# tinyadder_r3.net
KiCad netlist of a schematic drawn in EAGLE
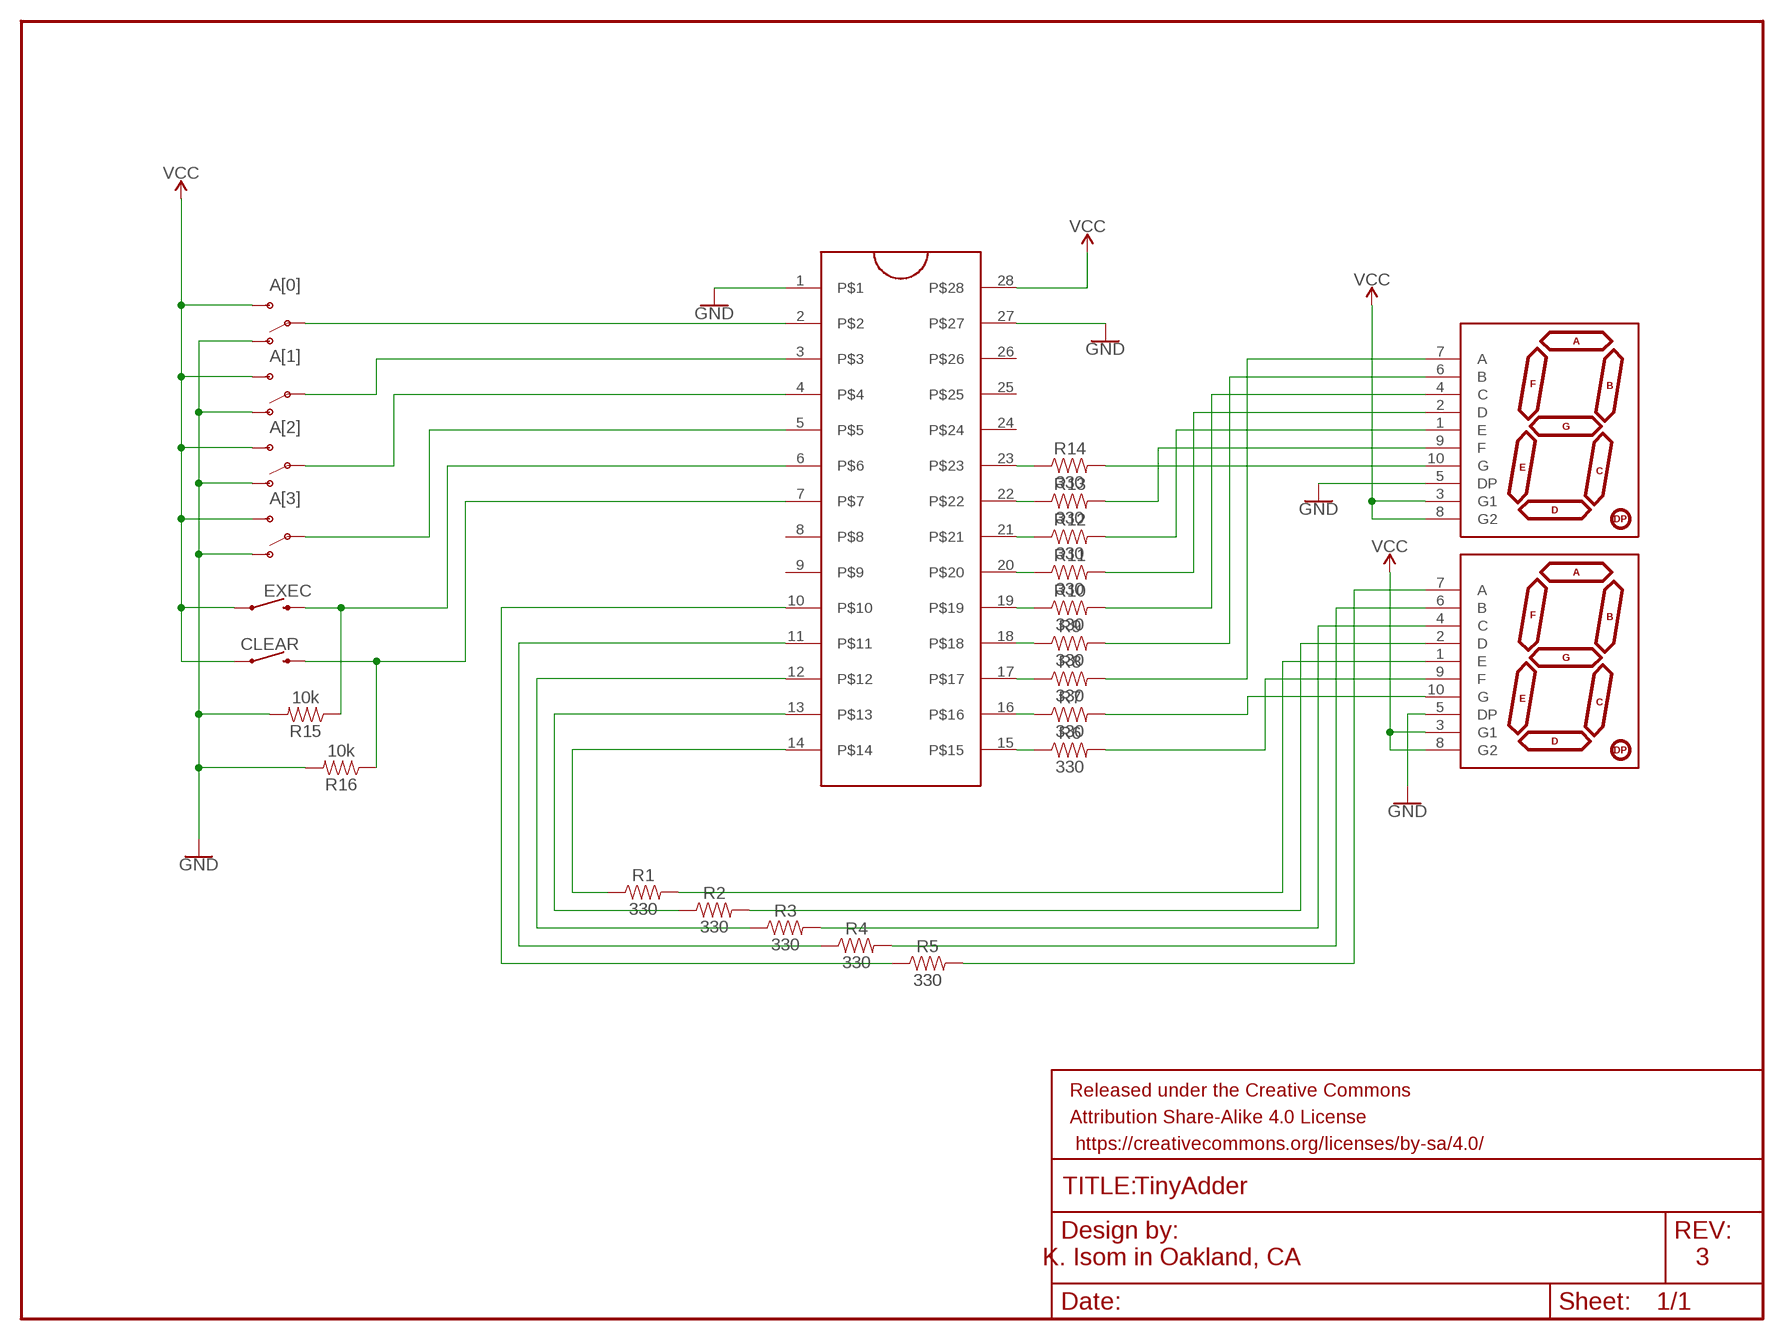
[diagram p0: schematic, sheet 1]

(export (version "E")
  (design (tool "Eeschema 10.0.6"))
  (components
    (comp (ref "A[0]")
      (value "SWITCH-SPDT-PTH-11.6X4.0MM")
      (footprint "eagle-import:SWITCH_SPDT_PTH_11.6X4.0MM")
      (libsource (lib "eagle-import") (part "SWITCH-SPDT-PTH-11.6X4.0MM"))
    )
    (comp (ref "A[1]")
      (value "SWITCH-SPDT-PTH-11.6X4.0MM")
      (footprint "eagle-import:SWITCH_SPDT_PTH_11.6X4.0MM")
      (libsource (lib "eagle-import") (part "SWITCH-SPDT-PTH-11.6X4.0MM"))
    )
    (comp (ref "A[2]")
      (value "SWITCH-SPDT-PTH-11.6X4.0MM")
      (footprint "eagle-import:SWITCH_SPDT_PTH_11.6X4.0MM")
      (libsource (lib "eagle-import") (part "SWITCH-SPDT-PTH-11.6X4.0MM"))
    )
    (comp (ref "A[3]")
      (value "SWITCH-SPDT-PTH-11.6X4.0MM")
      (footprint "eagle-import:SWITCH_SPDT_PTH_11.6X4.0MM")
      (libsource (lib "eagle-import") (part "SWITCH-SPDT-PTH-11.6X4.0MM"))
    )
    (comp (ref "CLEAR")
      (value "MOMENTARY-SWITCH-SPST-PTH-6.0MM")
      (footprint "eagle-import:TACTILE_SWITCH_PTH_6.0MM")
      (libsource (lib "eagle-import") (part "MOMENTARY-SWITCH-SPST-PTH-6.0MM"))
    )
    (comp (ref "EXEC")
      (value "MOMENTARY-SWITCH-SPST-PTH-6.0MM")
      (footprint "eagle-import:TACTILE_SWITCH_PTH_6.0MM")
      (libsource (lib "eagle-import") (part "MOMENTARY-SWITCH-SPST-PTH-6.0MM"))
    )
    (comp (ref "FRAME1")
      (value "FRAME-LETTER")
      (footprint "eagle-import:CREATIVE_COMMONS")
      (libsource (lib "eagle-import") (part "FRAME-LETTER"))
    )
    (comp (ref "J1")
      (value "ZIFSOCKET-28-3\"")
      (footprint "eagle-import:DIL28-3-ZIF_SOCKET")
      (libsource (lib "eagle-import") (part "ZIFSOCKET-28-3{dblquote}"))
    )
    (comp (ref "R1")
      (value "330")
      (footprint "eagle-import:AXIAL-0.3")
      (libsource (lib "eagle-import") (part "330OHM-HORIZ-1/10W-5%"))
    )
    (comp (ref "R2")
      (value "330")
      (footprint "eagle-import:AXIAL-0.3")
      (libsource (lib "eagle-import") (part "330OHM-HORIZ-1/10W-5%"))
    )
    (comp (ref "R3")
      (value "330")
      (footprint "eagle-import:AXIAL-0.3")
      (libsource (lib "eagle-import") (part "330OHM-HORIZ-1/10W-5%"))
    )
    (comp (ref "R4")
      (value "330")
      (footprint "eagle-import:AXIAL-0.3")
      (libsource (lib "eagle-import") (part "330OHM-HORIZ-1/10W-5%"))
    )
    (comp (ref "R5")
      (value "330")
      (footprint "eagle-import:AXIAL-0.3")
      (libsource (lib "eagle-import") (part "330OHM-HORIZ-1/10W-5%"))
    )
    (comp (ref "R6")
      (value "330")
      (footprint "eagle-import:AXIAL-0.3")
      (libsource (lib "eagle-import") (part "330OHM-HORIZ-1/10W-5%"))
    )
    (comp (ref "R7")
      (value "330")
      (footprint "eagle-import:AXIAL-0.3")
      (libsource (lib "eagle-import") (part "330OHM-HORIZ-1/10W-5%"))
    )
    (comp (ref "R8")
      (value "330")
      (footprint "eagle-import:AXIAL-0.3")
      (libsource (lib "eagle-import") (part "330OHM-HORIZ-1/10W-5%"))
    )
    (comp (ref "R9")
      (value "330")
      (footprint "eagle-import:AXIAL-0.3")
      (libsource (lib "eagle-import") (part "330OHM-HORIZ-1/10W-5%"))
    )
    (comp (ref "R10")
      (value "330")
      (footprint "eagle-import:AXIAL-0.3")
      (libsource (lib "eagle-import") (part "330OHM-HORIZ-1/10W-5%"))
    )
    (comp (ref "R11")
      (value "330")
      (footprint "eagle-import:AXIAL-0.3")
      (libsource (lib "eagle-import") (part "330OHM-HORIZ-1/10W-5%"))
    )
    (comp (ref "R12")
      (value "330")
      (footprint "eagle-import:AXIAL-0.3")
      (libsource (lib "eagle-import") (part "330OHM-HORIZ-1/10W-5%"))
    )
    (comp (ref "R13")
      (value "330")
      (footprint "eagle-import:AXIAL-0.3")
      (libsource (lib "eagle-import") (part "330OHM-HORIZ-1/10W-5%"))
    )
    (comp (ref "R14")
      (value "330")
      (footprint "eagle-import:AXIAL-0.3")
      (libsource (lib "eagle-import") (part "330OHM-HORIZ-1/10W-5%"))
    )
    (comp (ref "R15")
      (value "10k")
      (footprint "eagle-import:AXIAL-0.3")
      (libsource (lib "eagle-import") (part "10KOHM-HORIZ-1/4W-1%"))
    )
    (comp (ref "R16")
      (value "10k")
      (footprint "eagle-import:AXIAL-0.3")
      (libsource (lib "eagle-import") (part "10KOHM-HORIZ-1/4W-1%"))
    )
    (comp (ref "U$1")
      (value "YSD-1601AR4B-8")
      (footprint "eagle-import:7-SEGMENT-1_PTH")
      (libsource (lib "eagle-import") (part "7-SEGMENT-1DIGIT-1INCH-RED"))
    )
    (comp (ref "U$2")
      (value "YSD-1601AR4B-8")
      (footprint "eagle-import:7-SEGMENT-1_PTH")
      (libsource (lib "eagle-import") (part "7-SEGMENT-1DIGIT-1INCH-RED"))
    )
  )
  (nets
    (net (code "1") (name "GND") (class "Default")
      (node (ref "A[0]") (pin "1") (pinfunction "O_1") (pintype "passive"))
      (node (ref "A[1]") (pin "1") (pinfunction "O_1") (pintype "passive"))
      (node (ref "A[2]") (pin "1") (pinfunction "O_1") (pintype "passive"))
      (node (ref "A[3]") (pin "1") (pinfunction "O_1") (pintype "passive"))
      (node (ref "J1") (pin "1") (pinfunction "P$1_1") (pintype "bidirectional"))
      (node (ref "J1") (pin "27") (pinfunction "P$27_27") (pintype "bidirectional"))
      (node (ref "R15") (pin "P$2") (pinfunction "2_P$2") (pintype "passive"))
      (node (ref "R16") (pin "P$2") (pinfunction "2_P$2") (pintype "passive"))
      (node (ref "U$1") (pin "5") (pinfunction "DP_5") (pintype "bidirectional"))
      (node (ref "U$2") (pin "5") (pinfunction "DP_5") (pintype "bidirectional"))
    )
    (net (code "2") (name "Net-(A[0]-P)") (class "Default")
      (node (ref "A[0]") (pin "2") (pinfunction "P_2") (pintype "passive"))
      (node (ref "J1") (pin "2") (pinfunction "P$2_2") (pintype "bidirectional"))
    )
    (net (code "3") (name "Net-(A[1]-P)") (class "Default")
      (node (ref "A[1]") (pin "2") (pinfunction "P_2") (pintype "passive"))
      (node (ref "J1") (pin "3") (pinfunction "P$3_3") (pintype "bidirectional"))
    )
    (net (code "4") (name "Net-(A[2]-P)") (class "Default")
      (node (ref "A[2]") (pin "2") (pinfunction "P_2") (pintype "passive"))
      (node (ref "J1") (pin "4") (pinfunction "P$4_4") (pintype "bidirectional"))
    )
    (net (code "5") (name "Net-(A[3]-P)") (class "Default")
      (node (ref "A[3]") (pin "2") (pinfunction "P_2") (pintype "passive"))
      (node (ref "J1") (pin "5") (pinfunction "P$5_5") (pintype "bidirectional"))
    )
    (net (code "6") (name "Net-(CLEAR-2)") (class "Default")
      (node (ref "CLEAR") (pin "3") (pinfunction "2_3") (pintype "passive"))
      (node (ref "J1") (pin "7") (pinfunction "P$7_7") (pintype "bidirectional"))
      (node (ref "R16") (pin "P$1") (pinfunction "1_P$1") (pintype "passive"))
    )
    (net (code "7") (name "Net-(EXEC-2)") (class "Default")
      (node (ref "EXEC") (pin "3") (pinfunction "2_3") (pintype "passive"))
      (node (ref "J1") (pin "6") (pinfunction "P$6_6") (pintype "bidirectional"))
      (node (ref "R15") (pin "P$1") (pinfunction "1_P$1") (pintype "passive"))
    )
    (net (code "8") (name "Net-(J1-P$10)") (class "Default")
      (node (ref "J1") (pin "10") (pinfunction "P$10_10") (pintype "bidirectional"))
      (node (ref "R5") (pin "P$1") (pinfunction "1_P$1") (pintype "passive"))
    )
    (net (code "9") (name "Net-(J1-P$11)") (class "Default")
      (node (ref "J1") (pin "11") (pinfunction "P$11_11") (pintype "bidirectional"))
      (node (ref "R4") (pin "P$1") (pinfunction "1_P$1") (pintype "passive"))
    )
    (net (code "10") (name "Net-(J1-P$12)") (class "Default")
      (node (ref "J1") (pin "12") (pinfunction "P$12_12") (pintype "bidirectional"))
      (node (ref "R3") (pin "P$1") (pinfunction "1_P$1") (pintype "passive"))
    )
    (net (code "11") (name "Net-(J1-P$13)") (class "Default")
      (node (ref "J1") (pin "13") (pinfunction "P$13_13") (pintype "bidirectional"))
      (node (ref "R2") (pin "P$1") (pinfunction "1_P$1") (pintype "passive"))
    )
    (net (code "12") (name "Net-(J1-P$14)") (class "Default")
      (node (ref "J1") (pin "14") (pinfunction "P$14_14") (pintype "bidirectional"))
      (node (ref "R1") (pin "P$1") (pinfunction "1_P$1") (pintype "passive"))
    )
    (net (code "13") (name "Net-(J1-P$15)") (class "Default")
      (node (ref "J1") (pin "15") (pinfunction "P$15_15") (pintype "bidirectional"))
      (node (ref "R6") (pin "P$1") (pinfunction "1_P$1") (pintype "passive"))
    )
    (net (code "14") (name "Net-(J1-P$16)") (class "Default")
      (node (ref "J1") (pin "16") (pinfunction "P$16_16") (pintype "bidirectional"))
      (node (ref "R7") (pin "P$1") (pinfunction "1_P$1") (pintype "passive"))
    )
    (net (code "15") (name "Net-(J1-P$17)") (class "Default")
      (node (ref "J1") (pin "17") (pinfunction "P$17_17") (pintype "bidirectional"))
      (node (ref "R8") (pin "P$1") (pinfunction "1_P$1") (pintype "passive"))
    )
    (net (code "16") (name "Net-(J1-P$18)") (class "Default")
      (node (ref "J1") (pin "18") (pinfunction "P$18_18") (pintype "bidirectional"))
      (node (ref "R9") (pin "P$1") (pinfunction "1_P$1") (pintype "passive"))
    )
    (net (code "17") (name "Net-(J1-P$19)") (class "Default")
      (node (ref "J1") (pin "19") (pinfunction "P$19_19") (pintype "bidirectional"))
      (node (ref "R10") (pin "P$1") (pinfunction "1_P$1") (pintype "passive"))
    )
    (net (code "18") (name "Net-(J1-P$20)") (class "Default")
      (node (ref "J1") (pin "20") (pinfunction "P$20_20") (pintype "bidirectional"))
      (node (ref "R11") (pin "P$1") (pinfunction "1_P$1") (pintype "passive"))
    )
    (net (code "19") (name "Net-(J1-P$21)") (class "Default")
      (node (ref "J1") (pin "21") (pinfunction "P$21_21") (pintype "bidirectional"))
      (node (ref "R12") (pin "P$1") (pinfunction "1_P$1") (pintype "passive"))
    )
    (net (code "20") (name "Net-(J1-P$22)") (class "Default")
      (node (ref "J1") (pin "22") (pinfunction "P$22_22") (pintype "bidirectional"))
      (node (ref "R13") (pin "P$1") (pinfunction "1_P$1") (pintype "passive"))
    )
    (net (code "21") (name "Net-(J1-P$23)") (class "Default")
      (node (ref "J1") (pin "23") (pinfunction "P$23_23") (pintype "bidirectional"))
      (node (ref "R14") (pin "P$1") (pinfunction "1_P$1") (pintype "passive"))
    )
    (net (code "22") (name "Net-(R1-2)") (class "Default")
      (node (ref "R1") (pin "P$2") (pinfunction "2_P$2") (pintype "passive"))
      (node (ref "U$2") (pin "1") (pinfunction "E_1") (pintype "bidirectional"))
    )
    (net (code "23") (name "Net-(R2-2)") (class "Default")
      (node (ref "R2") (pin "P$2") (pinfunction "2_P$2") (pintype "passive"))
      (node (ref "U$2") (pin "2") (pinfunction "D_2") (pintype "bidirectional"))
    )
    (net (code "24") (name "Net-(R3-2)") (class "Default")
      (node (ref "R3") (pin "P$2") (pinfunction "2_P$2") (pintype "passive"))
      (node (ref "U$2") (pin "4") (pinfunction "C_4") (pintype "bidirectional"))
    )
    (net (code "25") (name "Net-(R4-2)") (class "Default")
      (node (ref "R4") (pin "P$2") (pinfunction "2_P$2") (pintype "passive"))
      (node (ref "U$2") (pin "6") (pinfunction "B_6") (pintype "bidirectional"))
    )
    (net (code "26") (name "Net-(R5-2)") (class "Default")
      (node (ref "R5") (pin "P$2") (pinfunction "2_P$2") (pintype "passive"))
      (node (ref "U$2") (pin "7") (pinfunction "A_7") (pintype "bidirectional"))
    )
    (net (code "27") (name "Net-(R6-2)") (class "Default")
      (node (ref "R6") (pin "P$2") (pinfunction "2_P$2") (pintype "passive"))
      (node (ref "U$2") (pin "9") (pinfunction "F_9") (pintype "bidirectional"))
    )
    (net (code "28") (name "Net-(R7-2)") (class "Default")
      (node (ref "R7") (pin "P$2") (pinfunction "2_P$2") (pintype "passive"))
      (node (ref "U$2") (pin "10") (pinfunction "G_10") (pintype "bidirectional"))
    )
    (net (code "29") (name "Net-(R8-2)") (class "Default")
      (node (ref "R8") (pin "P$2") (pinfunction "2_P$2") (pintype "passive"))
      (node (ref "U$1") (pin "7") (pinfunction "A_7") (pintype "bidirectional"))
    )
    (net (code "30") (name "Net-(R9-2)") (class "Default")
      (node (ref "R9") (pin "P$2") (pinfunction "2_P$2") (pintype "passive"))
      (node (ref "U$1") (pin "6") (pinfunction "B_6") (pintype "bidirectional"))
    )
    (net (code "31") (name "Net-(R10-2)") (class "Default")
      (node (ref "R10") (pin "P$2") (pinfunction "2_P$2") (pintype "passive"))
      (node (ref "U$1") (pin "4") (pinfunction "C_4") (pintype "bidirectional"))
    )
    (net (code "32") (name "Net-(R11-2)") (class "Default")
      (node (ref "R11") (pin "P$2") (pinfunction "2_P$2") (pintype "passive"))
      (node (ref "U$1") (pin "2") (pinfunction "D_2") (pintype "bidirectional"))
    )
    (net (code "33") (name "Net-(R12-2)") (class "Default")
      (node (ref "R12") (pin "P$2") (pinfunction "2_P$2") (pintype "passive"))
      (node (ref "U$1") (pin "1") (pinfunction "E_1") (pintype "bidirectional"))
    )
    (net (code "34") (name "Net-(R13-2)") (class "Default")
      (node (ref "R13") (pin "P$2") (pinfunction "2_P$2") (pintype "passive"))
      (node (ref "U$1") (pin "9") (pinfunction "F_9") (pintype "bidirectional"))
    )
    (net (code "35") (name "Net-(R14-2)") (class "Default")
      (node (ref "R14") (pin "P$2") (pinfunction "2_P$2") (pintype "passive"))
      (node (ref "U$1") (pin "10") (pinfunction "G_10") (pintype "bidirectional"))
    )
    (net (code "36") (name "VCC") (class "Default")
      (node (ref "A[0]") (pin "3") (pinfunction "S_3") (pintype "passive"))
      (node (ref "A[1]") (pin "3") (pinfunction "S_3") (pintype "passive"))
      (node (ref "A[2]") (pin "3") (pinfunction "S_3") (pintype "passive"))
      (node (ref "A[3]") (pin "3") (pinfunction "S_3") (pintype "passive"))
      (node (ref "CLEAR") (pin "1") (pinfunction "1_1") (pintype "passive"))
      (node (ref "EXEC") (pin "1") (pinfunction "1_1") (pintype "passive"))
      (node (ref "J1") (pin "28") (pinfunction "P$28_28") (pintype "bidirectional"))
      (node (ref "U$1") (pin "3") (pinfunction "G1_3") (pintype "bidirectional"))
      (node (ref "U$1") (pin "8") (pinfunction "G2_8") (pintype "bidirectional"))
      (node (ref "U$2") (pin "3") (pinfunction "G1_3") (pintype "bidirectional"))
      (node (ref "U$2") (pin "8") (pinfunction "G2_8") (pintype "bidirectional"))
    )
    (net (code "37") (name "unconnected-(J1-P$8-Pad8)") (class "Default")
      (node (ref "J1") (pin "8") (pinfunction "P$8_8") (pintype "bidirectional"))
    )
    (net (code "38") (name "unconnected-(J1-P$9-Pad9)") (class "Default")
      (node (ref "J1") (pin "9") (pinfunction "P$9_9") (pintype "bidirectional"))
    )
    (net (code "39") (name "unconnected-(J1-P$24-Pad24)") (class "Default")
      (node (ref "J1") (pin "24") (pinfunction "P$24_24") (pintype "bidirectional"))
    )
    (net (code "40") (name "unconnected-(J1-P$25-Pad25)") (class "Default")
      (node (ref "J1") (pin "25") (pinfunction "P$25_25") (pintype "bidirectional"))
    )
    (net (code "41") (name "unconnected-(J1-P$26-Pad26)") (class "Default")
      (node (ref "J1") (pin "26") (pinfunction "P$26_26") (pintype "bidirectional"))
    )
  )
)
